# serializer_24x.net
KiCad netlist of a schematic drawn in EAGLE
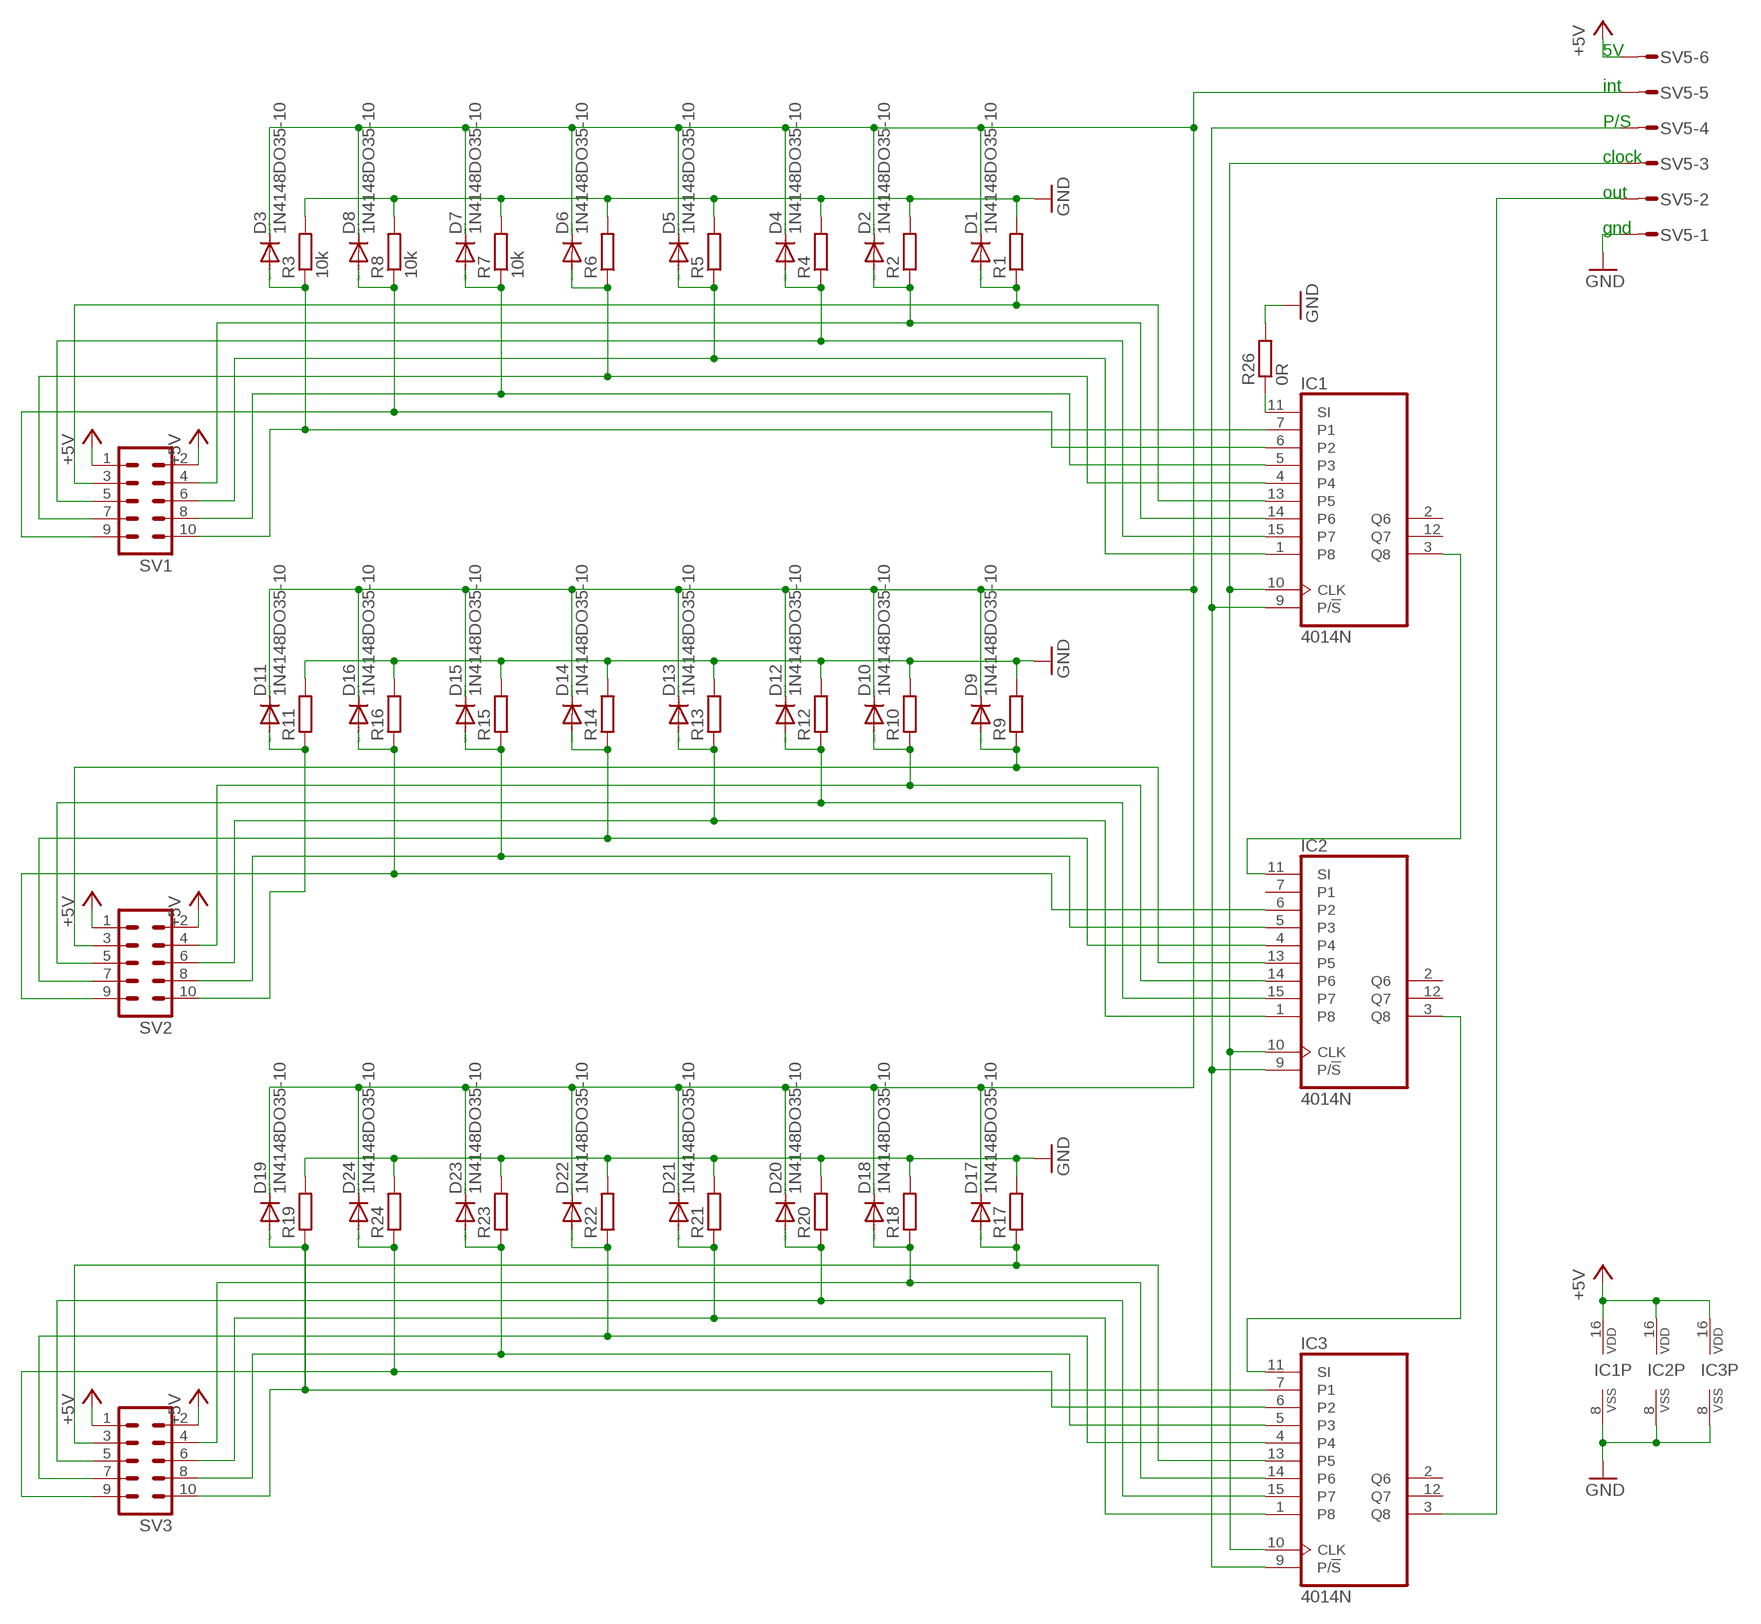
[diagram p0: schematic, sheet 1]

(export (version "E")
  (design (tool "Eeschema 10.0.6"))
  (components
    (comp (ref "D1")
      (value "1N4148DO35-10")
      (footprint "eagle-import:DO35-10")
      (libsource (lib "eagle-import") (part "1N4148DO35-10"))
    )
    (comp (ref "D2")
      (value "1N4148DO35-10")
      (footprint "eagle-import:DO35-10")
      (libsource (lib "eagle-import") (part "1N4148DO35-10"))
    )
    (comp (ref "D3")
      (value "1N4148DO35-10")
      (footprint "eagle-import:DO35-10")
      (libsource (lib "eagle-import") (part "1N4148DO35-10"))
    )
    (comp (ref "D4")
      (value "1N4148DO35-10")
      (footprint "eagle-import:DO35-10")
      (libsource (lib "eagle-import") (part "1N4148DO35-10"))
    )
    (comp (ref "D5")
      (value "1N4148DO35-10")
      (footprint "eagle-import:DO35-10")
      (libsource (lib "eagle-import") (part "1N4148DO35-10"))
    )
    (comp (ref "D6")
      (value "1N4148DO35-10")
      (footprint "eagle-import:DO35-10")
      (libsource (lib "eagle-import") (part "1N4148DO35-10"))
    )
    (comp (ref "D7")
      (value "1N4148DO35-10")
      (footprint "eagle-import:DO35-10")
      (libsource (lib "eagle-import") (part "1N4148DO35-10"))
    )
    (comp (ref "D8")
      (value "1N4148DO35-10")
      (footprint "eagle-import:DO35-10")
      (libsource (lib "eagle-import") (part "1N4148DO35-10"))
    )
    (comp (ref "D9")
      (value "1N4148DO35-10")
      (footprint "eagle-import:DO35-10")
      (libsource (lib "eagle-import") (part "1N4148DO35-10"))
    )
    (comp (ref "D10")
      (value "1N4148DO35-10")
      (footprint "eagle-import:DO35-10")
      (libsource (lib "eagle-import") (part "1N4148DO35-10"))
    )
    (comp (ref "D11")
      (value "1N4148DO35-10")
      (footprint "eagle-import:DO35-10")
      (libsource (lib "eagle-import") (part "1N4148DO35-10"))
    )
    (comp (ref "D12")
      (value "1N4148DO35-10")
      (footprint "eagle-import:DO35-10")
      (libsource (lib "eagle-import") (part "1N4148DO35-10"))
    )
    (comp (ref "D13")
      (value "1N4148DO35-10")
      (footprint "eagle-import:DO35-10")
      (libsource (lib "eagle-import") (part "1N4148DO35-10"))
    )
    (comp (ref "D14")
      (value "1N4148DO35-10")
      (footprint "eagle-import:DO35-10")
      (libsource (lib "eagle-import") (part "1N4148DO35-10"))
    )
    (comp (ref "D15")
      (value "1N4148DO35-10")
      (footprint "eagle-import:DO35-10")
      (libsource (lib "eagle-import") (part "1N4148DO35-10"))
    )
    (comp (ref "D16")
      (value "1N4148DO35-10")
      (footprint "eagle-import:DO35-10")
      (libsource (lib "eagle-import") (part "1N4148DO35-10"))
    )
    (comp (ref "D17")
      (value "1N4148DO35-10")
      (footprint "eagle-import:DO35-10")
      (libsource (lib "eagle-import") (part "1N4148DO35-10"))
    )
    (comp (ref "D18")
      (value "1N4148DO35-10")
      (footprint "eagle-import:DO35-10")
      (libsource (lib "eagle-import") (part "1N4148DO35-10"))
    )
    (comp (ref "D19")
      (value "1N4148DO35-10")
      (footprint "eagle-import:DO35-10")
      (libsource (lib "eagle-import") (part "1N4148DO35-10"))
    )
    (comp (ref "D20")
      (value "1N4148DO35-10")
      (footprint "eagle-import:DO35-10")
      (libsource (lib "eagle-import") (part "1N4148DO35-10"))
    )
    (comp (ref "D21")
      (value "1N4148DO35-10")
      (footprint "eagle-import:DO35-10")
      (libsource (lib "eagle-import") (part "1N4148DO35-10"))
    )
    (comp (ref "D22")
      (value "1N4148DO35-10")
      (footprint "eagle-import:DO35-10")
      (libsource (lib "eagle-import") (part "1N4148DO35-10"))
    )
    (comp (ref "D23")
      (value "1N4148DO35-10")
      (footprint "eagle-import:DO35-10")
      (libsource (lib "eagle-import") (part "1N4148DO35-10"))
    )
    (comp (ref "D24")
      (value "1N4148DO35-10")
      (footprint "eagle-import:DO35-10")
      (libsource (lib "eagle-import") (part "1N4148DO35-10"))
    )
    (comp (ref "IC1")
      (value "4014N")
      (footprint "eagle-import:DIL16")
      (libsource (lib "eagle-import") (part "4014N"))
    )
    (comp (ref "IC2")
      (value "4014N")
      (footprint "eagle-import:DIL16")
      (libsource (lib "eagle-import") (part "4014N"))
    )
    (comp (ref "IC3")
      (value "4014N")
      (footprint "eagle-import:DIL16")
      (libsource (lib "eagle-import") (part "4014N"))
    )
    (comp (ref "R1")
      (value "R-EU_M1206")
      (footprint "eagle-import:M1206")
      (libsource (lib "eagle-import") (part "R-EU_M1206"))
    )
    (comp (ref "R2")
      (value "R-EU_M1206")
      (footprint "eagle-import:M1206")
      (libsource (lib "eagle-import") (part "R-EU_M1206"))
    )
    (comp (ref "R3")
      (value "10k")
      (footprint "eagle-import:M1206")
      (libsource (lib "eagle-import") (part "R-EU_M1206"))
    )
    (comp (ref "R4")
      (value "R-EU_M1206")
      (footprint "eagle-import:M1206")
      (libsource (lib "eagle-import") (part "R-EU_M1206"))
    )
    (comp (ref "R5")
      (value "R-EU_M1206")
      (footprint "eagle-import:M1206")
      (libsource (lib "eagle-import") (part "R-EU_M1206"))
    )
    (comp (ref "R6")
      (value "R-EU_M1206")
      (footprint "eagle-import:M1206")
      (libsource (lib "eagle-import") (part "R-EU_M1206"))
    )
    (comp (ref "R7")
      (value "10k")
      (footprint "eagle-import:M1206")
      (libsource (lib "eagle-import") (part "R-EU_M1206"))
    )
    (comp (ref "R8")
      (value "10k")
      (footprint "eagle-import:M1206")
      (libsource (lib "eagle-import") (part "R-EU_M1206"))
    )
    (comp (ref "R9")
      (value "R-EU_M1206")
      (footprint "eagle-import:M1206")
      (libsource (lib "eagle-import") (part "R-EU_M1206"))
    )
    (comp (ref "R10")
      (value "R-EU_M1206")
      (footprint "eagle-import:M1206")
      (libsource (lib "eagle-import") (part "R-EU_M1206"))
    )
    (comp (ref "R11")
      (value "R-EU_M1206")
      (footprint "eagle-import:M1206")
      (libsource (lib "eagle-import") (part "R-EU_M1206"))
    )
    (comp (ref "R12")
      (value "R-EU_M1206")
      (footprint "eagle-import:M1206")
      (libsource (lib "eagle-import") (part "R-EU_M1206"))
    )
    (comp (ref "R13")
      (value "R-EU_M1206")
      (footprint "eagle-import:M1206")
      (libsource (lib "eagle-import") (part "R-EU_M1206"))
    )
    (comp (ref "R14")
      (value "R-EU_M1206")
      (footprint "eagle-import:M1206")
      (libsource (lib "eagle-import") (part "R-EU_M1206"))
    )
    (comp (ref "R15")
      (value "R-EU_M1206")
      (footprint "eagle-import:M1206")
      (libsource (lib "eagle-import") (part "R-EU_M1206"))
    )
    (comp (ref "R16")
      (value "R-EU_M1206")
      (footprint "eagle-import:M1206")
      (libsource (lib "eagle-import") (part "R-EU_M1206"))
    )
    (comp (ref "R17")
      (value "R-EU_M1206")
      (footprint "eagle-import:M1206")
      (libsource (lib "eagle-import") (part "R-EU_M1206"))
    )
    (comp (ref "R18")
      (value "R-EU_M1206")
      (footprint "eagle-import:M1206")
      (libsource (lib "eagle-import") (part "R-EU_M1206"))
    )
    (comp (ref "R19")
      (value "R-EU_M1206")
      (footprint "eagle-import:M1206")
      (libsource (lib "eagle-import") (part "R-EU_M1206"))
    )
    (comp (ref "R20")
      (value "R-EU_M1206")
      (footprint "eagle-import:M1206")
      (libsource (lib "eagle-import") (part "R-EU_M1206"))
    )
    (comp (ref "R21")
      (value "R-EU_M1206")
      (footprint "eagle-import:M1206")
      (libsource (lib "eagle-import") (part "R-EU_M1206"))
    )
    (comp (ref "R22")
      (value "R-EU_M1206")
      (footprint "eagle-import:M1206")
      (libsource (lib "eagle-import") (part "R-EU_M1206"))
    )
    (comp (ref "R23")
      (value "R-EU_M1206")
      (footprint "eagle-import:M1206")
      (libsource (lib "eagle-import") (part "R-EU_M1206"))
    )
    (comp (ref "R24")
      (value "R-EU_M1206")
      (footprint "eagle-import:M1206")
      (libsource (lib "eagle-import") (part "R-EU_M1206"))
    )
    (comp (ref "R26")
      (value "0R")
      (footprint "eagle-import:M1206")
      (libsource (lib "eagle-import") (part "R-EU_M1206"))
    )
    (comp (ref "SV1")
      (value "ML10")
      (footprint "eagle-import:ML10")
      (libsource (lib "eagle-import") (part "ML10"))
    )
    (comp (ref "SV2")
      (value "ML10")
      (footprint "eagle-import:ML10")
      (libsource (lib "eagle-import") (part "ML10"))
    )
    (comp (ref "SV3")
      (value "ML10")
      (footprint "eagle-import:ML10")
      (libsource (lib "eagle-import") (part "ML10"))
    )
    (comp (ref "SV5")
      (value "S06P")
      (footprint "eagle-import:S06P")
      (libsource (lib "eagle-import") (part "S06P"))
    )
  )
  (nets
    (net (code "1") (name "+5V") (class "Default")
      (node (ref "IC1") (pin "16") (pinfunction "VDD_16") (pintype "power_in"))
      (node (ref "IC2") (pin "16") (pinfunction "VDD_16") (pintype "power_in"))
      (node (ref "IC3") (pin "16") (pinfunction "VDD_16") (pintype "power_in"))
      (node (ref "SV1") (pin "1") (pinfunction "1_1") (pintype "passive"))
      (node (ref "SV1") (pin "2") (pinfunction "2_2") (pintype "passive"))
      (node (ref "SV2") (pin "1") (pinfunction "1_1") (pintype "passive"))
      (node (ref "SV2") (pin "2") (pinfunction "2_2") (pintype "passive"))
      (node (ref "SV3") (pin "1") (pinfunction "1_1") (pintype "passive"))
      (node (ref "SV3") (pin "2") (pinfunction "2_2") (pintype "passive"))
      (node (ref "SV5") (pin "6") (pinfunction "S_6") (pintype "passive"))
    )
    (net (code "2") (name "GND") (class "Default")
      (node (ref "IC1") (pin "8") (pinfunction "VSS_8") (pintype "power_in"))
      (node (ref "IC2") (pin "8") (pinfunction "VSS_8") (pintype "power_in"))
      (node (ref "IC3") (pin "8") (pinfunction "VSS_8") (pintype "power_in"))
      (node (ref "R1") (pin "2") (pinfunction "2_2") (pintype "passive"))
      (node (ref "R10") (pin "2") (pinfunction "2_2") (pintype "passive"))
      (node (ref "R11") (pin "2") (pinfunction "2_2") (pintype "passive"))
      (node (ref "R12") (pin "2") (pinfunction "2_2") (pintype "passive"))
      (node (ref "R13") (pin "2") (pinfunction "2_2") (pintype "passive"))
      (node (ref "R14") (pin "2") (pinfunction "2_2") (pintype "passive"))
      (node (ref "R15") (pin "2") (pinfunction "2_2") (pintype "passive"))
      (node (ref "R16") (pin "2") (pinfunction "2_2") (pintype "passive"))
      (node (ref "R17") (pin "2") (pinfunction "2_2") (pintype "passive"))
      (node (ref "R18") (pin "2") (pinfunction "2_2") (pintype "passive"))
      (node (ref "R19") (pin "2") (pinfunction "2_2") (pintype "passive"))
      (node (ref "R2") (pin "2") (pinfunction "2_2") (pintype "passive"))
      (node (ref "R20") (pin "2") (pinfunction "2_2") (pintype "passive"))
      (node (ref "R21") (pin "2") (pinfunction "2_2") (pintype "passive"))
      (node (ref "R22") (pin "2") (pinfunction "2_2") (pintype "passive"))
      (node (ref "R23") (pin "2") (pinfunction "2_2") (pintype "passive"))
      (node (ref "R24") (pin "2") (pinfunction "2_2") (pintype "passive"))
      (node (ref "R26") (pin "2") (pinfunction "2_2") (pintype "passive"))
      (node (ref "R3") (pin "2") (pinfunction "2_2") (pintype "passive"))
      (node (ref "R4") (pin "2") (pinfunction "2_2") (pintype "passive"))
      (node (ref "R5") (pin "2") (pinfunction "2_2") (pintype "passive"))
      (node (ref "R6") (pin "2") (pinfunction "2_2") (pintype "passive"))
      (node (ref "R7") (pin "2") (pinfunction "2_2") (pintype "passive"))
      (node (ref "R8") (pin "2") (pinfunction "2_2") (pintype "passive"))
      (node (ref "R9") (pin "2") (pinfunction "2_2") (pintype "passive"))
      (node (ref "SV5") (pin "1") (pinfunction "S_1") (pintype "passive"))
    )
    (net (code "3") (name "Net-(D11-PadA)") (class "Default")
      (node (ref "D11") (pin "A") (pinfunction "A_A") (pintype "passive"))
      (node (ref "R11") (pin "1") (pinfunction "1_1") (pintype "passive"))
      (node (ref "SV2") (pin "10") (pinfunction "10_10") (pintype "passive"))
    )
    (net (code "4") (name "Net-(IC1A-CLK)") (class "Default")
      (node (ref "IC1") (pin "10") (pinfunction "CLK_10") (pintype "input"))
      (node (ref "IC2") (pin "10") (pinfunction "CLK_10") (pintype "input"))
      (node (ref "IC3") (pin "10") (pinfunction "CLK_10") (pintype "input"))
      (node (ref "SV5") (pin "3") (pinfunction "S_3") (pintype "passive"))
    )
    (net (code "5") (name "Net-(IC1A-P1)") (class "Default")
      (node (ref "D3") (pin "A") (pinfunction "A_A") (pintype "passive"))
      (node (ref "IC1") (pin "7") (pinfunction "P1_7") (pintype "input"))
      (node (ref "R3") (pin "1") (pinfunction "1_1") (pintype "passive"))
      (node (ref "SV1") (pin "10") (pinfunction "10_10") (pintype "passive"))
    )
    (net (code "6") (name "Net-(IC1A-P2)") (class "Default")
      (node (ref "D8") (pin "A") (pinfunction "A_A") (pintype "passive"))
      (node (ref "IC1") (pin "6") (pinfunction "P2_6") (pintype "input"))
      (node (ref "R8") (pin "1") (pinfunction "1_1") (pintype "passive"))
      (node (ref "SV1") (pin "9") (pinfunction "9_9") (pintype "passive"))
    )
    (net (code "7") (name "Net-(IC1A-P3)") (class "Default")
      (node (ref "D7") (pin "A") (pinfunction "A_A") (pintype "passive"))
      (node (ref "IC1") (pin "5") (pinfunction "P3_5") (pintype "input"))
      (node (ref "R7") (pin "1") (pinfunction "1_1") (pintype "passive"))
      (node (ref "SV1") (pin "8") (pinfunction "8_8") (pintype "passive"))
    )
    (net (code "8") (name "Net-(IC1A-P4)") (class "Default")
      (node (ref "D6") (pin "A") (pinfunction "A_A") (pintype "passive"))
      (node (ref "IC1") (pin "4") (pinfunction "P4_4") (pintype "input"))
      (node (ref "R6") (pin "1") (pinfunction "1_1") (pintype "passive"))
      (node (ref "SV1") (pin "7") (pinfunction "7_7") (pintype "passive"))
    )
    (net (code "9") (name "Net-(IC1A-P5)") (class "Default")
      (node (ref "D1") (pin "A") (pinfunction "A_A") (pintype "passive"))
      (node (ref "IC1") (pin "13") (pinfunction "P5_13") (pintype "input"))
      (node (ref "R1") (pin "1") (pinfunction "1_1") (pintype "passive"))
      (node (ref "SV1") (pin "3") (pinfunction "3_3") (pintype "passive"))
    )
    (net (code "10") (name "Net-(IC1A-P6)") (class "Default")
      (node (ref "D2") (pin "A") (pinfunction "A_A") (pintype "passive"))
      (node (ref "IC1") (pin "14") (pinfunction "P6_14") (pintype "input"))
      (node (ref "R2") (pin "1") (pinfunction "1_1") (pintype "passive"))
      (node (ref "SV1") (pin "4") (pinfunction "4_4") (pintype "passive"))
    )
    (net (code "11") (name "Net-(IC1A-P7)") (class "Default")
      (node (ref "D4") (pin "A") (pinfunction "A_A") (pintype "passive"))
      (node (ref "IC1") (pin "15") (pinfunction "P7_15") (pintype "input"))
      (node (ref "R4") (pin "1") (pinfunction "1_1") (pintype "passive"))
      (node (ref "SV1") (pin "5") (pinfunction "5_5") (pintype "passive"))
    )
    (net (code "12") (name "Net-(IC1A-P8)") (class "Default")
      (node (ref "D5") (pin "A") (pinfunction "A_A") (pintype "passive"))
      (node (ref "IC1") (pin "1") (pinfunction "P8_1") (pintype "input"))
      (node (ref "R5") (pin "1") (pinfunction "1_1") (pintype "passive"))
      (node (ref "SV1") (pin "6") (pinfunction "6_6") (pintype "passive"))
    )
    (net (code "13") (name "Net-(IC1A-P{slash}~{S})") (class "Default")
      (node (ref "IC1") (pin "9") (pinfunction "P/~{S}_9") (pintype "input"))
      (node (ref "IC2") (pin "9") (pinfunction "P/~{S}_9") (pintype "input"))
      (node (ref "IC3") (pin "9") (pinfunction "P/~{S}_9") (pintype "input"))
      (node (ref "SV5") (pin "4") (pinfunction "S_4") (pintype "passive"))
    )
    (net (code "14") (name "Net-(IC1A-Q8)") (class "Default")
      (node (ref "IC1") (pin "3") (pinfunction "Q8_3") (pintype "output"))
      (node (ref "IC2") (pin "11") (pinfunction "SI_11") (pintype "input"))
    )
    (net (code "15") (name "Net-(IC1A-SI)") (class "Default")
      (node (ref "IC1") (pin "11") (pinfunction "SI_11") (pintype "input"))
      (node (ref "R26") (pin "1") (pinfunction "1_1") (pintype "passive"))
    )
    (net (code "16") (name "Net-(IC2A-P2)") (class "Default")
      (node (ref "D16") (pin "A") (pinfunction "A_A") (pintype "passive"))
      (node (ref "IC2") (pin "6") (pinfunction "P2_6") (pintype "input"))
      (node (ref "R16") (pin "1") (pinfunction "1_1") (pintype "passive"))
      (node (ref "SV2") (pin "9") (pinfunction "9_9") (pintype "passive"))
    )
    (net (code "17") (name "Net-(IC2A-P3)") (class "Default")
      (node (ref "D15") (pin "A") (pinfunction "A_A") (pintype "passive"))
      (node (ref "IC2") (pin "5") (pinfunction "P3_5") (pintype "input"))
      (node (ref "R15") (pin "1") (pinfunction "1_1") (pintype "passive"))
      (node (ref "SV2") (pin "8") (pinfunction "8_8") (pintype "passive"))
    )
    (net (code "18") (name "Net-(IC2A-P4)") (class "Default")
      (node (ref "D14") (pin "A") (pinfunction "A_A") (pintype "passive"))
      (node (ref "IC2") (pin "4") (pinfunction "P4_4") (pintype "input"))
      (node (ref "R14") (pin "1") (pinfunction "1_1") (pintype "passive"))
      (node (ref "SV2") (pin "7") (pinfunction "7_7") (pintype "passive"))
    )
    (net (code "19") (name "Net-(IC2A-P5)") (class "Default")
      (node (ref "D9") (pin "A") (pinfunction "A_A") (pintype "passive"))
      (node (ref "IC2") (pin "13") (pinfunction "P5_13") (pintype "input"))
      (node (ref "R9") (pin "1") (pinfunction "1_1") (pintype "passive"))
      (node (ref "SV2") (pin "3") (pinfunction "3_3") (pintype "passive"))
    )
    (net (code "20") (name "Net-(IC2A-P6)") (class "Default")
      (node (ref "D10") (pin "A") (pinfunction "A_A") (pintype "passive"))
      (node (ref "IC2") (pin "14") (pinfunction "P6_14") (pintype "input"))
      (node (ref "R10") (pin "1") (pinfunction "1_1") (pintype "passive"))
      (node (ref "SV2") (pin "4") (pinfunction "4_4") (pintype "passive"))
    )
    (net (code "21") (name "Net-(IC2A-P7)") (class "Default")
      (node (ref "D12") (pin "A") (pinfunction "A_A") (pintype "passive"))
      (node (ref "IC2") (pin "15") (pinfunction "P7_15") (pintype "input"))
      (node (ref "R12") (pin "1") (pinfunction "1_1") (pintype "passive"))
      (node (ref "SV2") (pin "5") (pinfunction "5_5") (pintype "passive"))
    )
    (net (code "22") (name "Net-(IC2A-P8)") (class "Default")
      (node (ref "D13") (pin "A") (pinfunction "A_A") (pintype "passive"))
      (node (ref "IC2") (pin "1") (pinfunction "P8_1") (pintype "input"))
      (node (ref "R13") (pin "1") (pinfunction "1_1") (pintype "passive"))
      (node (ref "SV2") (pin "6") (pinfunction "6_6") (pintype "passive"))
    )
    (net (code "23") (name "Net-(IC2A-Q8)") (class "Default")
      (node (ref "IC2") (pin "3") (pinfunction "Q8_3") (pintype "output"))
      (node (ref "IC3") (pin "11") (pinfunction "SI_11") (pintype "input"))
    )
    (net (code "24") (name "Net-(IC3A-P1)") (class "Default")
      (node (ref "D19") (pin "A") (pinfunction "A_A") (pintype "passive"))
      (node (ref "IC3") (pin "7") (pinfunction "P1_7") (pintype "input"))
      (node (ref "R19") (pin "1") (pinfunction "1_1") (pintype "passive"))
      (node (ref "SV3") (pin "10") (pinfunction "10_10") (pintype "passive"))
    )
    (net (code "25") (name "Net-(IC3A-P2)") (class "Default")
      (node (ref "D24") (pin "A") (pinfunction "A_A") (pintype "passive"))
      (node (ref "IC3") (pin "6") (pinfunction "P2_6") (pintype "input"))
      (node (ref "R24") (pin "1") (pinfunction "1_1") (pintype "passive"))
      (node (ref "SV3") (pin "9") (pinfunction "9_9") (pintype "passive"))
    )
    (net (code "26") (name "Net-(IC3A-P3)") (class "Default")
      (node (ref "D23") (pin "A") (pinfunction "A_A") (pintype "passive"))
      (node (ref "IC3") (pin "5") (pinfunction "P3_5") (pintype "input"))
      (node (ref "R23") (pin "1") (pinfunction "1_1") (pintype "passive"))
      (node (ref "SV3") (pin "8") (pinfunction "8_8") (pintype "passive"))
    )
    (net (code "27") (name "Net-(IC3A-P4)") (class "Default")
      (node (ref "D22") (pin "A") (pinfunction "A_A") (pintype "passive"))
      (node (ref "IC3") (pin "4") (pinfunction "P4_4") (pintype "input"))
      (node (ref "R22") (pin "1") (pinfunction "1_1") (pintype "passive"))
      (node (ref "SV3") (pin "7") (pinfunction "7_7") (pintype "passive"))
    )
    (net (code "28") (name "Net-(IC3A-P5)") (class "Default")
      (node (ref "D17") (pin "A") (pinfunction "A_A") (pintype "passive"))
      (node (ref "IC3") (pin "13") (pinfunction "P5_13") (pintype "input"))
      (node (ref "R17") (pin "1") (pinfunction "1_1") (pintype "passive"))
      (node (ref "SV3") (pin "3") (pinfunction "3_3") (pintype "passive"))
    )
    (net (code "29") (name "Net-(IC3A-P6)") (class "Default")
      (node (ref "D18") (pin "A") (pinfunction "A_A") (pintype "passive"))
      (node (ref "IC3") (pin "14") (pinfunction "P6_14") (pintype "input"))
      (node (ref "R18") (pin "1") (pinfunction "1_1") (pintype "passive"))
      (node (ref "SV3") (pin "4") (pinfunction "4_4") (pintype "passive"))
    )
    (net (code "30") (name "Net-(IC3A-P7)") (class "Default")
      (node (ref "D20") (pin "A") (pinfunction "A_A") (pintype "passive"))
      (node (ref "IC3") (pin "15") (pinfunction "P7_15") (pintype "input"))
      (node (ref "R20") (pin "1") (pinfunction "1_1") (pintype "passive"))
      (node (ref "SV3") (pin "5") (pinfunction "5_5") (pintype "passive"))
    )
    (net (code "31") (name "Net-(IC3A-P8)") (class "Default")
      (node (ref "D21") (pin "A") (pinfunction "A_A") (pintype "passive"))
      (node (ref "IC3") (pin "1") (pinfunction "P8_1") (pintype "input"))
      (node (ref "R21") (pin "1") (pinfunction "1_1") (pintype "passive"))
      (node (ref "SV3") (pin "6") (pinfunction "6_6") (pintype "passive"))
    )
    (net (code "32") (name "Net-(IC3A-Q8)") (class "Default")
      (node (ref "IC3") (pin "3") (pinfunction "Q8_3") (pintype "output"))
      (node (ref "SV5") (pin "2") (pinfunction "S_2") (pintype "passive"))
    )
    (net (code "33") (name "Net-(SV5E-S)") (class "Default")
      (node (ref "D1") (pin "C") (pinfunction "C_C") (pintype "passive"))
      (node (ref "D10") (pin "C") (pinfunction "C_C") (pintype "passive"))
      (node (ref "D11") (pin "C") (pinfunction "C_C") (pintype "passive"))
      (node (ref "D12") (pin "C") (pinfunction "C_C") (pintype "passive"))
      (node (ref "D13") (pin "C") (pinfunction "C_C") (pintype "passive"))
      (node (ref "D14") (pin "C") (pinfunction "C_C") (pintype "passive"))
      (node (ref "D15") (pin "C") (pinfunction "C_C") (pintype "passive"))
      (node (ref "D16") (pin "C") (pinfunction "C_C") (pintype "passive"))
      (node (ref "D17") (pin "C") (pinfunction "C_C") (pintype "passive"))
      (node (ref "D18") (pin "C") (pinfunction "C_C") (pintype "passive"))
      (node (ref "D19") (pin "C") (pinfunction "C_C") (pintype "passive"))
      (node (ref "D2") (pin "C") (pinfunction "C_C") (pintype "passive"))
      (node (ref "D20") (pin "C") (pinfunction "C_C") (pintype "passive"))
      (node (ref "D21") (pin "C") (pinfunction "C_C") (pintype "passive"))
      (node (ref "D22") (pin "C") (pinfunction "C_C") (pintype "passive"))
      (node (ref "D23") (pin "C") (pinfunction "C_C") (pintype "passive"))
      (node (ref "D24") (pin "C") (pinfunction "C_C") (pintype "passive"))
      (node (ref "D3") (pin "C") (pinfunction "C_C") (pintype "passive"))
      (node (ref "D4") (pin "C") (pinfunction "C_C") (pintype "passive"))
      (node (ref "D5") (pin "C") (pinfunction "C_C") (pintype "passive"))
      (node (ref "D6") (pin "C") (pinfunction "C_C") (pintype "passive"))
      (node (ref "D7") (pin "C") (pinfunction "C_C") (pintype "passive"))
      (node (ref "D8") (pin "C") (pinfunction "C_C") (pintype "passive"))
      (node (ref "D9") (pin "C") (pinfunction "C_C") (pintype "passive"))
      (node (ref "SV5") (pin "5") (pinfunction "S_5") (pintype "passive"))
    )
    (net (code "34") (name "unconnected-(IC1A-Q6-Pad2)") (class "Default")
      (node (ref "IC1") (pin "2") (pinfunction "Q6_2") (pintype "output"))
    )
    (net (code "35") (name "unconnected-(IC1A-Q7-Pad12)") (class "Default")
      (node (ref "IC1") (pin "12") (pinfunction "Q7_12") (pintype "output"))
    )
    (net (code "36") (name "unconnected-(IC2A-P1-Pad7)") (class "Default")
      (node (ref "IC2") (pin "7") (pinfunction "P1_7") (pintype "input"))
    )
    (net (code "37") (name "unconnected-(IC2A-Q6-Pad2)") (class "Default")
      (node (ref "IC2") (pin "2") (pinfunction "Q6_2") (pintype "output"))
    )
    (net (code "38") (name "unconnected-(IC2A-Q7-Pad12)") (class "Default")
      (node (ref "IC2") (pin "12") (pinfunction "Q7_12") (pintype "output"))
    )
    (net (code "39") (name "unconnected-(IC3A-Q6-Pad2)") (class "Default")
      (node (ref "IC3") (pin "2") (pinfunction "Q6_2") (pintype "output"))
    )
    (net (code "40") (name "unconnected-(IC3A-Q7-Pad12)") (class "Default")
      (node (ref "IC3") (pin "12") (pinfunction "Q7_12") (pintype "output"))
    )
  )
)
